# ATEM_Tally_Shield_v1_0.net
KiCad netlist of a schematic drawn in EAGLE
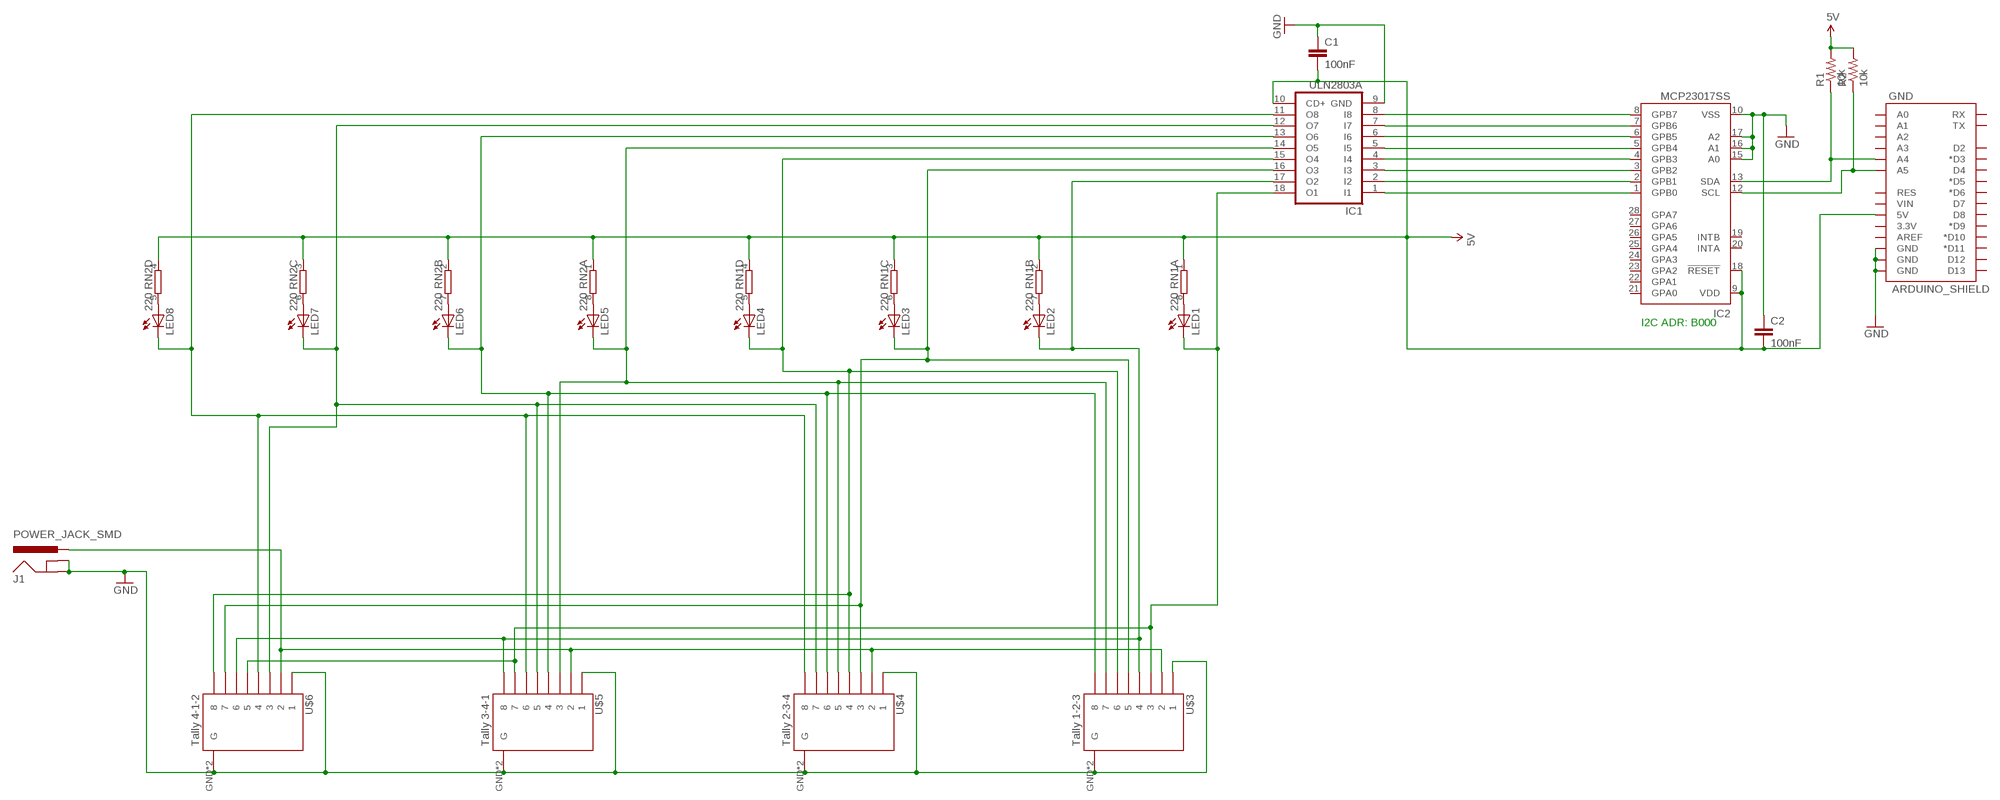
[diagram p0: schematic, sheet 1]

(export (version "E")
  (design (tool "Eeschema 10.0.6"))
  (components
    (comp (ref "C1")
      (value "100nF")
      (footprint "eagle-import:0805")
      (libsource (lib "eagle-import") (part "CAP0805"))
    )
    (comp (ref "C2")
      (value "100nF")
      (footprint "eagle-import:0603-CAP")
      (libsource (lib "eagle-import") (part "CAP0603-CAP"))
    )
    (comp (ref "GND")
      (value "ARDUINO_SHIELD")
      (footprint "eagle-import:ARDUINO_BOXSHIELD_NOHOLES")
      (libsource (lib "eagle-import") (part "ARDUINO_SHIELD"))
    )
    (comp (ref "IC1")
      (value "ULN2803A")
      (footprint "eagle-import:SO18W")
      (libsource (lib "eagle-import") (part "ULN2803ASO18W"))
    )
    (comp (ref "IC2")
      (value "MCP23017SS")
      (footprint "eagle-import:SSOP28")
      (fields (field (name "MF") "MICROCHIP") (field (name "MPN") "MCP23017-E/SS"))
      (libsource (lib "eagle-import") (part "MCP23017SS"))
    )
    (comp (ref "J1")
      (value "POWER_JACK_SMD")
      (footprint "eagle-import:POWER_JACK_SMD")
      (libsource (lib "eagle-import") (part "POWER_JACK_SMD"))
    )
    (comp (ref "LED1")
      (value "LEDSML0805")
      (footprint "eagle-import:SML0805")
      (libsource (lib "eagle-import") (part "LEDSML0805"))
    )
    (comp (ref "LED2")
      (value "LEDSML0805")
      (footprint "eagle-import:SML0805")
      (libsource (lib "eagle-import") (part "LEDSML0805"))
    )
    (comp (ref "LED3")
      (value "LEDSML0805")
      (footprint "eagle-import:SML0805")
      (libsource (lib "eagle-import") (part "LEDSML0805"))
    )
    (comp (ref "LED4")
      (value "LEDSML0805")
      (footprint "eagle-import:SML0805")
      (libsource (lib "eagle-import") (part "LEDSML0805"))
    )
    (comp (ref "LED5")
      (value "LEDSML0805")
      (footprint "eagle-import:SML0805")
      (libsource (lib "eagle-import") (part "LEDSML0805"))
    )
    (comp (ref "LED6")
      (value "LEDSML0805")
      (footprint "eagle-import:SML0805")
      (libsource (lib "eagle-import") (part "LEDSML0805"))
    )
    (comp (ref "LED7")
      (value "LEDSML0805")
      (footprint "eagle-import:SML0805")
      (libsource (lib "eagle-import") (part "LEDSML0805"))
    )
    (comp (ref "LED8")
      (value "LEDSML0805")
      (footprint "eagle-import:SML0805")
      (libsource (lib "eagle-import") (part "LEDSML0805"))
    )
    (comp (ref "R1")
      (value "10k")
      (footprint "eagle-import:0603-RES")
      (libsource (lib "eagle-import") (part "RESISTOR0603-RES"))
    )
    (comp (ref "R2")
      (value "10k")
      (footprint "eagle-import:0603-RES")
      (libsource (lib "eagle-import") (part "RESISTOR0603-RES"))
    )
    (comp (ref "RN1")
      (value "220")
      (footprint "eagle-import:CAY16_HAND")
      (libsource (lib "eagle-import") (part "4R-NCAY16"))
    )
    (comp (ref "RN2")
      (value "220")
      (footprint "eagle-import:CAY16_HAND")
      (libsource (lib "eagle-import") (part "4R-NCAY16"))
    )
    (comp (ref "U$3")
      (value "Tally 1-2-3")
      (footprint "eagle-import:RJ45-8_GND")
      (libsource (lib "eagle-import") (part "RJ45-8_GND"))
    )
    (comp (ref "U$4")
      (value "Tally 2-3-4")
      (footprint "eagle-import:RJ45-8_GND")
      (libsource (lib "eagle-import") (part "RJ45-8_GND"))
    )
    (comp (ref "U$5")
      (value "Tally 3-4-1")
      (footprint "eagle-import:RJ45-8_GND")
      (libsource (lib "eagle-import") (part "RJ45-8_GND"))
    )
    (comp (ref "U$6")
      (value "Tally 4-1-2")
      (footprint "eagle-import:RJ45-8_GND")
      (libsource (lib "eagle-import") (part "RJ45-8_GND"))
    )
  )
  (nets
    (net (code "1") (name "5V") (class "Default")
      (node (ref "C1") (pin "2") (pinfunction "2_2") (pintype "passive"))
      (node (ref "C2") (pin "2") (pinfunction "2_2") (pintype "passive"))
      (node (ref "GND") (pin "5V@0") (pinfunction "5V_5V@0") (pintype "bidirectional"))
      (node (ref "IC1") (pin "10") (pinfunction "CD+_10") (pintype "passive"))
      (node (ref "IC2") (pin "18") (pinfunction "~{RESET}_18") (pintype "input"))
      (node (ref "IC2") (pin "9") (pinfunction "VDD_9") (pintype "power_in"))
      (node (ref "R1") (pin "2") (pinfunction "2_2") (pintype "passive"))
      (node (ref "R2") (pin "2") (pinfunction "2_2") (pintype "passive"))
      (node (ref "RN1") (pin "1") (pinfunction "1_1") (pintype "passive"))
      (node (ref "RN1") (pin "2") (pinfunction "1_2") (pintype "passive"))
      (node (ref "RN1") (pin "3") (pinfunction "1_3") (pintype "passive"))
      (node (ref "RN1") (pin "4") (pinfunction "1_4") (pintype "passive"))
      (node (ref "RN2") (pin "1") (pinfunction "1_1") (pintype "passive"))
      (node (ref "RN2") (pin "2") (pinfunction "1_2") (pintype "passive"))
      (node (ref "RN2") (pin "3") (pinfunction "1_3") (pintype "passive"))
      (node (ref "RN2") (pin "4") (pinfunction "1_4") (pintype "passive"))
    )
    (net (code "2") (name "GND") (class "Default")
      (node (ref "C1") (pin "1") (pinfunction "1_1") (pintype "passive"))
      (node (ref "C2") (pin "1") (pinfunction "1_1") (pintype "passive"))
      (node (ref "GND") (pin "GND@0") (pinfunction "GND_GND@0") (pintype "bidirectional"))
      (node (ref "GND") (pin "GND@1") (pinfunction "GND_GND@1") (pintype "bidirectional"))
      (node (ref "GND") (pin "GND@4") (pinfunction "GND_GND@4") (pintype "bidirectional"))
      (node (ref "IC1") (pin "9") (pinfunction "GND_9") (pintype "power_in"))
      (node (ref "IC2") (pin "10") (pinfunction "VSS_10") (pintype "power_in"))
      (node (ref "IC2") (pin "15") (pinfunction "A0_15") (pintype "input"))
      (node (ref "IC2") (pin "16") (pinfunction "A1_16") (pintype "input"))
      (node (ref "IC2") (pin "17") (pinfunction "A2_17") (pintype "input"))
      (node (ref "J1") (pin "GND") (pinfunction "GND_GND") (pintype "bidirectional"))
      (node (ref "J1") (pin "SHUNT") (pinfunction "GNDBREAK_SHUNT") (pintype "bidirectional"))
      (node (ref "U$3") (pin "1") (pinfunction "1_1") (pintype "bidirectional"))
      (node (ref "U$3") (pin "GND") (pinfunction "G_GND") (pintype "power_in"))
      (node (ref "U$3") (pin "GND1") (pinfunction "G_GND1") (pintype "power_in"))
      (node (ref "U$4") (pin "1") (pinfunction "1_1") (pintype "bidirectional"))
      (node (ref "U$4") (pin "GND") (pinfunction "G_GND") (pintype "power_in"))
      (node (ref "U$4") (pin "GND1") (pinfunction "G_GND1") (pintype "power_in"))
      (node (ref "U$5") (pin "1") (pinfunction "1_1") (pintype "bidirectional"))
      (node (ref "U$5") (pin "GND") (pinfunction "G_GND") (pintype "power_in"))
      (node (ref "U$5") (pin "GND1") (pinfunction "G_GND1") (pintype "power_in"))
      (node (ref "U$6") (pin "1") (pinfunction "1_1") (pintype "bidirectional"))
      (node (ref "U$6") (pin "GND") (pinfunction "G_GND") (pintype "power_in"))
      (node (ref "U$6") (pin "GND1") (pinfunction "G_GND1") (pintype "power_in"))
    )
    (net (code "3") (name "Net-(IC1-I1)") (class "Default")
      (node (ref "IC1") (pin "1") (pinfunction "I1_1") (pintype "input"))
      (node (ref "IC2") (pin "1") (pinfunction "GPB0_1") (pintype "bidirectional"))
    )
    (net (code "4") (name "Net-(IC1-I2)") (class "Default")
      (node (ref "IC1") (pin "2") (pinfunction "I2_2") (pintype "input"))
      (node (ref "IC2") (pin "2") (pinfunction "GPB1_2") (pintype "bidirectional"))
    )
    (net (code "5") (name "Net-(IC1-I3)") (class "Default")
      (node (ref "IC1") (pin "3") (pinfunction "I3_3") (pintype "input"))
      (node (ref "IC2") (pin "3") (pinfunction "GPB2_3") (pintype "bidirectional"))
    )
    (net (code "6") (name "Net-(IC1-I4)") (class "Default")
      (node (ref "IC1") (pin "4") (pinfunction "I4_4") (pintype "input"))
      (node (ref "IC2") (pin "4") (pinfunction "GPB3_4") (pintype "bidirectional"))
    )
    (net (code "7") (name "Net-(IC1-I5)") (class "Default")
      (node (ref "IC1") (pin "5") (pinfunction "I5_5") (pintype "input"))
      (node (ref "IC2") (pin "5") (pinfunction "GPB4_5") (pintype "bidirectional"))
    )
    (net (code "8") (name "Net-(IC1-I6)") (class "Default")
      (node (ref "IC1") (pin "6") (pinfunction "I6_6") (pintype "input"))
      (node (ref "IC2") (pin "6") (pinfunction "GPB5_6") (pintype "bidirectional"))
    )
    (net (code "9") (name "Net-(IC1-I7)") (class "Default")
      (node (ref "IC1") (pin "7") (pinfunction "I7_7") (pintype "input"))
      (node (ref "IC2") (pin "7") (pinfunction "GPB6_7") (pintype "bidirectional"))
    )
    (net (code "10") (name "Net-(IC1-I8)") (class "Default")
      (node (ref "IC1") (pin "8") (pinfunction "I8_8") (pintype "input"))
      (node (ref "IC2") (pin "8") (pinfunction "GPB7_8") (pintype "bidirectional"))
    )
    (net (code "11") (name "Net-(IC1-O1)") (class "Default")
      (node (ref "IC1") (pin "18") (pinfunction "O1_18") (pintype "open_collector"))
      (node (ref "LED1") (pin "C") (pinfunction "C_C") (pintype "passive"))
      (node (ref "U$3") (pin "3") (pinfunction "3_3") (pintype "bidirectional"))
      (node (ref "U$5") (pin "7") (pinfunction "7_7") (pintype "bidirectional"))
      (node (ref "U$6") (pin "5") (pinfunction "5_5") (pintype "bidirectional"))
    )
    (net (code "12") (name "Net-(IC1-O2)") (class "Default")
      (node (ref "IC1") (pin "17") (pinfunction "O2_17") (pintype "open_collector"))
      (node (ref "LED2") (pin "C") (pinfunction "C_C") (pintype "passive"))
      (node (ref "U$3") (pin "4") (pinfunction "4_4") (pintype "bidirectional"))
      (node (ref "U$5") (pin "8") (pinfunction "8_8") (pintype "bidirectional"))
      (node (ref "U$6") (pin "6") (pinfunction "6_6") (pintype "bidirectional"))
    )
    (net (code "13") (name "Net-(IC1-O3)") (class "Default")
      (node (ref "IC1") (pin "16") (pinfunction "O3_16") (pintype "open_collector"))
      (node (ref "LED3") (pin "C") (pinfunction "C_C") (pintype "passive"))
      (node (ref "U$3") (pin "5") (pinfunction "5_5") (pintype "bidirectional"))
      (node (ref "U$4") (pin "3") (pinfunction "3_3") (pintype "bidirectional"))
      (node (ref "U$6") (pin "7") (pinfunction "7_7") (pintype "bidirectional"))
    )
    (net (code "14") (name "Net-(IC1-O4)") (class "Default")
      (node (ref "IC1") (pin "15") (pinfunction "O4_15") (pintype "open_collector"))
      (node (ref "LED4") (pin "C") (pinfunction "C_C") (pintype "passive"))
      (node (ref "U$3") (pin "6") (pinfunction "6_6") (pintype "bidirectional"))
      (node (ref "U$4") (pin "4") (pinfunction "4_4") (pintype "bidirectional"))
      (node (ref "U$6") (pin "8") (pinfunction "8_8") (pintype "bidirectional"))
    )
    (net (code "15") (name "Net-(IC1-O5)") (class "Default")
      (node (ref "IC1") (pin "14") (pinfunction "O5_14") (pintype "open_collector"))
      (node (ref "LED5") (pin "C") (pinfunction "C_C") (pintype "passive"))
      (node (ref "U$3") (pin "7") (pinfunction "7_7") (pintype "bidirectional"))
      (node (ref "U$4") (pin "5") (pinfunction "5_5") (pintype "bidirectional"))
      (node (ref "U$5") (pin "3") (pinfunction "3_3") (pintype "bidirectional"))
    )
    (net (code "16") (name "Net-(IC1-O6)") (class "Default")
      (node (ref "IC1") (pin "13") (pinfunction "O6_13") (pintype "open_collector"))
      (node (ref "LED6") (pin "C") (pinfunction "C_C") (pintype "passive"))
      (node (ref "U$3") (pin "8") (pinfunction "8_8") (pintype "bidirectional"))
      (node (ref "U$4") (pin "6") (pinfunction "6_6") (pintype "bidirectional"))
      (node (ref "U$5") (pin "4") (pinfunction "4_4") (pintype "bidirectional"))
    )
    (net (code "17") (name "Net-(IC1-O7)") (class "Default")
      (node (ref "IC1") (pin "12") (pinfunction "O7_12") (pintype "open_collector"))
      (node (ref "LED7") (pin "C") (pinfunction "C_C") (pintype "passive"))
      (node (ref "U$4") (pin "7") (pinfunction "7_7") (pintype "bidirectional"))
      (node (ref "U$5") (pin "5") (pinfunction "5_5") (pintype "bidirectional"))
      (node (ref "U$6") (pin "3") (pinfunction "3_3") (pintype "bidirectional"))
    )
    (net (code "18") (name "Net-(IC1-O8)") (class "Default")
      (node (ref "IC1") (pin "11") (pinfunction "O8_11") (pintype "open_collector"))
      (node (ref "LED8") (pin "C") (pinfunction "C_C") (pintype "passive"))
      (node (ref "U$4") (pin "8") (pinfunction "8_8") (pintype "bidirectional"))
      (node (ref "U$5") (pin "6") (pinfunction "6_6") (pintype "bidirectional"))
      (node (ref "U$6") (pin "4") (pinfunction "4_4") (pintype "bidirectional"))
    )
    (net (code "19") (name "Net-(IC2-SCL)") (class "Default")
      (node (ref "GND") (pin "A5") (pinfunction "A5_A5") (pintype "bidirectional"))
      (node (ref "IC2") (pin "12") (pinfunction "SCL_12") (pintype "input"))
      (node (ref "R2") (pin "1") (pinfunction "1_1") (pintype "passive"))
    )
    (net (code "20") (name "Net-(IC2-SDA)") (class "Default")
      (node (ref "GND") (pin "A4") (pinfunction "A4_A4") (pintype "bidirectional"))
      (node (ref "IC2") (pin "13") (pinfunction "SDA_13") (pintype "bidirectional"))
      (node (ref "R1") (pin "1") (pinfunction "1_1") (pintype "passive"))
    )
    (net (code "21") (name "Net-(J1-PadPWR)") (class "Default")
      (node (ref "J1") (pin "PWR") (pinfunction "PWR_PWR") (pintype "bidirectional"))
      (node (ref "U$3") (pin "2") (pinfunction "2_2") (pintype "bidirectional"))
      (node (ref "U$4") (pin "2") (pinfunction "2_2") (pintype "bidirectional"))
      (node (ref "U$5") (pin "2") (pinfunction "2_2") (pintype "bidirectional"))
      (node (ref "U$6") (pin "2") (pinfunction "2_2") (pintype "bidirectional"))
    )
    (net (code "22") (name "Net-(RN1A-2)") (class "Default")
      (node (ref "LED1") (pin "A") (pinfunction "A_A") (pintype "passive"))
      (node (ref "RN1") (pin "8") (pinfunction "2_8") (pintype "passive"))
    )
    (net (code "23") (name "Net-(RN1B-2)") (class "Default")
      (node (ref "LED2") (pin "A") (pinfunction "A_A") (pintype "passive"))
      (node (ref "RN1") (pin "7") (pinfunction "2_7") (pintype "passive"))
    )
    (net (code "24") (name "Net-(RN1C-2)") (class "Default")
      (node (ref "LED3") (pin "A") (pinfunction "A_A") (pintype "passive"))
      (node (ref "RN1") (pin "6") (pinfunction "2_6") (pintype "passive"))
    )
    (net (code "25") (name "Net-(RN1D-2)") (class "Default")
      (node (ref "LED4") (pin "A") (pinfunction "A_A") (pintype "passive"))
      (node (ref "RN1") (pin "5") (pinfunction "2_5") (pintype "passive"))
    )
    (net (code "26") (name "Net-(RN2A-2)") (class "Default")
      (node (ref "LED5") (pin "A") (pinfunction "A_A") (pintype "passive"))
      (node (ref "RN2") (pin "8") (pinfunction "2_8") (pintype "passive"))
    )
    (net (code "27") (name "Net-(RN2B-2)") (class "Default")
      (node (ref "LED6") (pin "A") (pinfunction "A_A") (pintype "passive"))
      (node (ref "RN2") (pin "7") (pinfunction "2_7") (pintype "passive"))
    )
    (net (code "28") (name "Net-(RN2C-2)") (class "Default")
      (node (ref "LED7") (pin "A") (pinfunction "A_A") (pintype "passive"))
      (node (ref "RN2") (pin "6") (pinfunction "2_6") (pintype "passive"))
    )
    (net (code "29") (name "Net-(RN2D-2)") (class "Default")
      (node (ref "LED8") (pin "A") (pinfunction "A_A") (pintype "passive"))
      (node (ref "RN2") (pin "5") (pinfunction "2_5") (pintype "passive"))
    )
    (net (code "30") (name "unconnected-(GND-*D3-Pad3)") (class "Default")
      (node (ref "GND") (pin "3") (pinfunction "*D3_3") (pintype "bidirectional"))
    )
    (net (code "31") (name "unconnected-(GND-*D5-Pad5)") (class "Default")
      (node (ref "GND") (pin "5") (pinfunction "*D5_5") (pintype "bidirectional"))
    )
    (net (code "32") (name "unconnected-(GND-*D6-Pad6)") (class "Default")
      (node (ref "GND") (pin "6") (pinfunction "*D6_6") (pintype "bidirectional"))
    )
    (net (code "33") (name "unconnected-(GND-*D9-Pad9)") (class "Default")
      (node (ref "GND") (pin "9") (pinfunction "*D9_9") (pintype "bidirectional"))
    )
    (net (code "34") (name "unconnected-(GND-*D10-Pad10)") (class "Default")
      (node (ref "GND") (pin "10") (pinfunction "*D10_10") (pintype "bidirectional"))
    )
    (net (code "35") (name "unconnected-(GND-*D11-Pad11)") (class "Default")
      (node (ref "GND") (pin "11") (pinfunction "*D11_11") (pintype "bidirectional"))
    )
    (net (code "36") (name "unconnected-(GND-D2-Pad2)") (class "Default")
      (node (ref "GND") (pin "2") (pinfunction "D2_2") (pintype "bidirectional"))
    )
    (net (code "37") (name "unconnected-(GND-D4-Pad4)") (class "Default")
      (node (ref "GND") (pin "4") (pinfunction "D4_4") (pintype "bidirectional"))
    )
    (net (code "38") (name "unconnected-(GND-D7-Pad7)") (class "Default")
      (node (ref "GND") (pin "7") (pinfunction "D7_7") (pintype "bidirectional"))
    )
    (net (code "39") (name "unconnected-(GND-D8-Pad8)") (class "Default")
      (node (ref "GND") (pin "8") (pinfunction "D8_8") (pintype "bidirectional"))
    )
    (net (code "40") (name "unconnected-(GND-D12-Pad12)") (class "Default")
      (node (ref "GND") (pin "12") (pinfunction "D12_12") (pintype "bidirectional"))
    )
    (net (code "41") (name "unconnected-(GND-D13-Pad13)") (class "Default")
      (node (ref "GND") (pin "13") (pinfunction "D13_13") (pintype "bidirectional"))
    )
    (net (code "42") (name "unconnected-(GND-Pad3.3V)") (class "Default")
      (node (ref "GND") (pin "3.3V") (pinfunction "3.3V_3.3V") (pintype "bidirectional"))
    )
    (net (code "43") (name "unconnected-(GND-PadA0)") (class "Default")
      (node (ref "GND") (pin "A0") (pinfunction "A0_A0") (pintype "bidirectional"))
    )
    (net (code "44") (name "unconnected-(GND-PadA1)") (class "Default")
      (node (ref "GND") (pin "A1") (pinfunction "A1_A1") (pintype "bidirectional"))
    )
    (net (code "45") (name "unconnected-(GND-PadA2)") (class "Default")
      (node (ref "GND") (pin "A2") (pinfunction "A2_A2") (pintype "bidirectional"))
    )
    (net (code "46") (name "unconnected-(GND-PadA3)") (class "Default")
      (node (ref "GND") (pin "A3") (pinfunction "A3_A3") (pintype "bidirectional"))
    )
    (net (code "47") (name "unconnected-(GND-PadAREF)") (class "Default")
      (node (ref "GND") (pin "AREF") (pinfunction "AREF_AREF") (pintype "bidirectional"))
    )
    (net (code "48") (name "unconnected-(GND-PadVIN)") (class "Default")
      (node (ref "GND") (pin "VIN") (pinfunction "VIN_VIN") (pintype "bidirectional"))
    )
    (net (code "49") (name "unconnected-(GND-RES-PadRESET)") (class "Default")
      (node (ref "GND") (pin "RESET") (pinfunction "RES_RESET") (pintype "bidirectional"))
    )
    (net (code "50") (name "unconnected-(GND-RX-Pad0)") (class "Default")
      (node (ref "GND") (pin "0") (pinfunction "RX_0") (pintype "bidirectional"))
    )
    (net (code "51") (name "unconnected-(GND-TX-Pad1)") (class "Default")
      (node (ref "GND") (pin "1") (pinfunction "TX_1") (pintype "bidirectional"))
    )
    (net (code "52") (name "unconnected-(IC2-GPA0-Pad21)") (class "Default")
      (node (ref "IC2") (pin "21") (pinfunction "GPA0_21") (pintype "bidirectional"))
    )
    (net (code "53") (name "unconnected-(IC2-GPA1-Pad22)") (class "Default")
      (node (ref "IC2") (pin "22") (pinfunction "GPA1_22") (pintype "bidirectional"))
    )
    (net (code "54") (name "unconnected-(IC2-GPA2-Pad23)") (class "Default")
      (node (ref "IC2") (pin "23") (pinfunction "GPA2_23") (pintype "bidirectional"))
    )
    (net (code "55") (name "unconnected-(IC2-GPA3-Pad24)") (class "Default")
      (node (ref "IC2") (pin "24") (pinfunction "GPA3_24") (pintype "bidirectional"))
    )
    (net (code "56") (name "unconnected-(IC2-GPA4-Pad25)") (class "Default")
      (node (ref "IC2") (pin "25") (pinfunction "GPA4_25") (pintype "bidirectional"))
    )
    (net (code "57") (name "unconnected-(IC2-GPA5-Pad26)") (class "Default")
      (node (ref "IC2") (pin "26") (pinfunction "GPA5_26") (pintype "bidirectional"))
    )
    (net (code "58") (name "unconnected-(IC2-GPA6-Pad27)") (class "Default")
      (node (ref "IC2") (pin "27") (pinfunction "GPA6_27") (pintype "bidirectional"))
    )
    (net (code "59") (name "unconnected-(IC2-GPA7-Pad28)") (class "Default")
      (node (ref "IC2") (pin "28") (pinfunction "GPA7_28") (pintype "bidirectional"))
    )
    (net (code "60") (name "unconnected-(IC2-INTA-Pad20)") (class "Default")
      (node (ref "IC2") (pin "20") (pinfunction "INTA_20") (pintype "output"))
    )
    (net (code "61") (name "unconnected-(IC2-INTB-Pad19)") (class "Default")
      (node (ref "IC2") (pin "19") (pinfunction "INTB_19") (pintype "output"))
    )
  )
)
